# 7_-ADC_Chip.net
KiCad netlist of a schematic drawn in Altium Designer
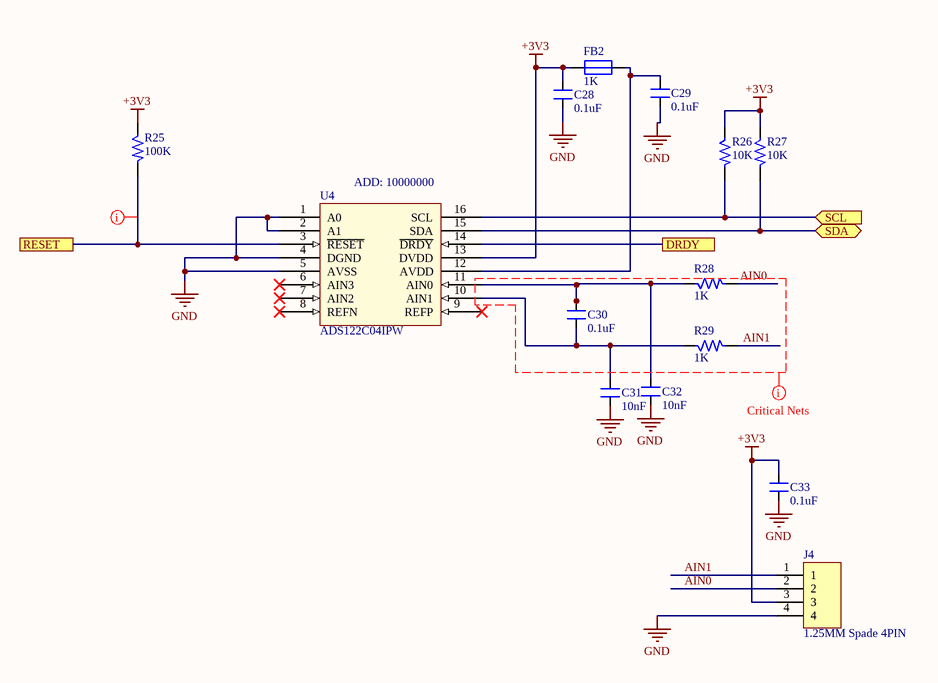
[diagram p0: (7)-ADC Chip.SchDoc]

(export (version "E")
  (design (tool "Eeschema 10.0.6"))
  (components
    (comp (ref "C28")
      (value "0.1uF")
      (footprint "CAP_0805")
      (description "0.1µF ±10% 50V Ceramic Capacitor X7R 0805 (2012 Metric)")
      (fields
        (field (name "MANUFACTURER") "Samsung")
        (field (name "MANUFACTURER PART NUMBER") "CL21B104KBCNNNC")
      )
      (libsource (lib "ESTEEMPCBLIB") (part "CAP_0.1uF-50V-10%-0805"))
    )
    (comp (ref "C29")
      (value "0.1uF")
      (footprint "CAP_0805")
      (description "0.1µF ±10% 50V Ceramic Capacitor X7R 0805 (2012 Metric)")
      (fields
        (field (name "MANUFACTURER") "Samsung")
        (field (name "MANUFACTURER PART NUMBER") "CL21B104KBCNNNC")
      )
      (libsource (lib "ESTEEMPCBLIB") (part "CAP_0.1uF-50V-10%-0805"))
    )
    (comp (ref "C30")
      (value "0.1uF")
      (footprint "CAP_0805")
      (description "0.1µF ±10% 50V Ceramic Capacitor X7R 0805 (2012 Metric)")
      (fields
        (field (name "MANUFACTURER") "Samsung")
        (field (name "MANUFACTURER PART NUMBER") "CL21B104KBCNNNC")
      )
      (libsource (lib "ESTEEMPCBLIB") (part "CAP_0.1uF-50V-10%-0805"))
    )
    (comp (ref "C31")
      (value "10nF")
      (footprint "CAP_0805")
      (description "10000pF ±10% 50V Ceramic Capacitor X7R 0805 (2012 Metric)")
      (fields
        (field (name "MANUFACTURER") "Samsung")
        (field (name "MANUFACTURER PART NUMBER") "C0805C103K5RECAUTO")
      )
      (libsource (lib "ESTEEMPCBLIB") (part "CAP_10nF-50V-10%-0805"))
    )
    (comp (ref "C32")
      (value "10nF")
      (footprint "CAP_0805")
      (description "10000pF ±10% 50V Ceramic Capacitor X7R 0805 (2012 Metric)")
      (fields
        (field (name "MANUFACTURER") "Samsung")
        (field (name "MANUFACTURER PART NUMBER") "C0805C103K5RECAUTO")
      )
      (libsource (lib "ESTEEMPCBLIB") (part "CAP_10nF-50V-10%-0805"))
    )
    (comp (ref "C33")
      (value "0.1uF")
      (footprint "CAP_0805")
      (description "0.1µF ±10% 50V Ceramic Capacitor X7R 0805 (2012 Metric)")
      (fields
        (field (name "MANUFACTURER") "Samsung")
        (field (name "MANUFACTURER PART NUMBER") "CL21B104KBCNNNC")
      )
      (libsource (lib "ESTEEMPCBLIB") (part "CAP_0.1uF-50V-10%-0805"))
    )
    (comp (ref "FB2")
      (value "1K")
      (footprint "IND_0805")
      (description "1 kOhms @ 100MHz 1 Power Line Ferrite Bead 0805 (2012 Metric) 1.6A")
      (fields
        (field (name "MANUFACTURER") "Laird")
        (field (name "MANUFACTURER PART NUMBER") "BLM21SP102SH1D")
      )
      (libsource (lib "ESTEEMPCBLIB") (part "FB_1K-100MHZ-1.6A-0805"))
    )
    (comp (ref "J4")
      (value "1.25MM Spade 4PIN")
      (footprint "CON4_50_653004117322_TH_RA")
      (description "4 Pins, 1 Row 1.25mm Pitch, right angle Connector, male")
      (fields (field (name "MANUFACTURER PART NUMBER") "653004117322") (field (name "MANUFACTURER") "JST"))
      (libsource (lib "ESTEEMPCBLIB") (part "CON-PLG_4X1-50-RA-TH"))
    )
    (comp (ref "R25")
      (value "100K")
      (footprint "RES_0603")
      (description "100 kOhms ±1% 0.1W, 1/10W Chip Resistor 0603 (1608 Metric) Automotive AEC-Q200 Thick Film")
      (fields
        (field (name "MANUFACTURER") "Stackpole Electronics")
        (field (name "MANUFACTURER PART NUMBER") "RMCF0603FT100K")
      )
      (libsource (lib "ESTEEMPCBLIB") (part "RES_100K-0.1W-1%-0603"))
    )
    (comp (ref "R26")
      (value "10K")
      (footprint "RES_0603")
      (description "10 kOhms ±1% 0.1W, 1/10W Chip Resistor 0603 (1608 Metric) Automotive AEC-Q200 Thick Film")
      (fields (field (name "MANUFACTURER") "Walsin") (field (name "MANUFACTURER PART NUMBER") "WR06X1002FTL"))
      (libsource (lib "ESTEEMPCBLIB") (part "RES_10K-0.1W-1%-0603"))
    )
    (comp (ref "R27")
      (value "10K")
      (footprint "RES_0603")
      (description "10 kOhms ±1% 0.1W, 1/10W Chip Resistor 0603 (1608 Metric) Automotive AEC-Q200 Thick Film")
      (fields (field (name "MANUFACTURER") "Walsin") (field (name "MANUFACTURER PART NUMBER") "WR06X1002FTL"))
      (libsource (lib "ESTEEMPCBLIB") (part "RES_10K-0.1W-1%-0603"))
    )
    (comp (ref "R28")
      (value "1K")
      (footprint "RES_0603")
      (description "1 kOhms ±1% 0.1W, 1/10W Chip Resistor 0603 (1608 Metric) Automotive AEC-Q200 Thick Film")
      (fields (field (name "MANUFACTURER") "Walsin") (field (name "MANUFACTURER PART NUMBER") "WR06X1001FTL"))
      (libsource (lib "ESTEEMPCBLIB") (part "RES_1K-0.1W-1%-0603"))
    )
    (comp (ref "R29")
      (value "1K")
      (footprint "RES_0603")
      (description "1 kOhms ±1% 0.1W, 1/10W Chip Resistor 0603 (1608 Metric) Automotive AEC-Q200 Thick Film")
      (fields (field (name "MANUFACTURER") "Walsin") (field (name "MANUFACTURER PART NUMBER") "WR06X1001FTL"))
      (libsource (lib "ESTEEMPCBLIB") (part "RES_1K-0.1W-1%-0603"))
    )
    (comp (ref "U4")
      (value "ADS122C04IPW")
      (footprint "TSSOP16_25-59_294_54X14_SMT")
      (description "24 Bit Analog to Digital Converter 4 Input 1 Sigma-Delta 16-TSSOP")
      (fields (field (name "MANUFACTURER") "Texas Instruments"))
      (libsource (lib "ESTEEMPCBLIB") (part "IC_ADS122C04IPW"))
    )
  )
  (nets
    (net (code "1") (name "+3V3") (class "Default")
      (node (ref "C28") (pin "2") (pinfunction "2_2") (pintype "passive"))
      (node (ref "C33") (pin "2") (pinfunction "2_2") (pintype "passive"))
      (node (ref "FB2") (pin "1") (pinfunction "1_1") (pintype "passive"))
      (node (ref "J4") (pin "3") (pinfunction "3_3") (pintype "passive"))
      (node (ref "R25") (pin "1") (pinfunction "1_1") (pintype "passive"))
      (node (ref "R26") (pin "1") (pinfunction "1_1") (pintype "passive"))
      (node (ref "R27") (pin "1") (pinfunction "1_1") (pintype "passive"))
      (node (ref "U4") (pin "13") (pinfunction "DVDD_13") (pintype "power_in"))
    )
    (net (code "2") (name "/AIN0") (class "Default")
      (node (ref "J4") (pin "2") (pinfunction "2_2") (pintype "passive"))
      (node (ref "R28") (pin "2") (pinfunction "2_2") (pintype "passive"))
    )
    (net (code "3") (name "/AIN1") (class "Default")
      (node (ref "J4") (pin "1") (pinfunction "1_1") (pintype "passive"))
      (node (ref "R29") (pin "2") (pinfunction "2_2") (pintype "passive"))
    )
    (net (code "4") (name "/DRDY") (class "Default")
      (node (ref "U4") (pin "14") (pinfunction "DRDY_14") (pintype "input"))
    )
    (net (code "5") (name "/RESET") (class "Default")
      (node (ref "R25") (pin "2") (pinfunction "2_2") (pintype "passive"))
      (node (ref "U4") (pin "3") (pinfunction "RESET_3") (pintype "input"))
    )
    (net (code "6") (name "/SCL") (class "Default")
      (node (ref "R26") (pin "2") (pinfunction "2_2") (pintype "passive"))
      (node (ref "U4") (pin "16") (pinfunction "SCL_16") (pintype "open_collector"))
    )
    (net (code "7") (name "/SDA") (class "Default")
      (node (ref "R27") (pin "2") (pinfunction "2_2") (pintype "passive"))
      (node (ref "U4") (pin "15") (pinfunction "SDA_15") (pintype "open_collector"))
    )
    (net (code "8") (name "GND") (class "Default")
      (node (ref "C28") (pin "1") (pinfunction "1_1") (pintype "passive"))
      (node (ref "C29") (pin "1") (pinfunction "1_1") (pintype "passive"))
      (node (ref "C31") (pin "2") (pinfunction "2_2") (pintype "passive"))
      (node (ref "C32") (pin "2") (pinfunction "2_2") (pintype "passive"))
      (node (ref "C33") (pin "1") (pinfunction "1_1") (pintype "passive"))
      (node (ref "J4") (pin "4") (pinfunction "4_4") (pintype "passive"))
      (node (ref "U4") (pin "1") (pinfunction "A0_1") (pintype "passive"))
      (node (ref "U4") (pin "2") (pinfunction "A1_2") (pintype "passive"))
      (node (ref "U4") (pin "4") (pinfunction "DGND_4") (pintype "power_in"))
      (node (ref "U4") (pin "5") (pinfunction "AVSS_5") (pintype "power_in"))
    )
    (net (code "9") (name "Net-(U4-AIN0)") (class "Default")
      (node (ref "C30") (pin "1") (pinfunction "1_1") (pintype "passive"))
      (node (ref "C32") (pin "1") (pinfunction "1_1") (pintype "passive"))
      (node (ref "R28") (pin "1") (pinfunction "1_1") (pintype "passive"))
      (node (ref "U4") (pin "11") (pinfunction "AIN0_11") (pintype "input"))
    )
    (net (code "10") (name "Net-(U4-AIN1)") (class "Default")
      (node (ref "C30") (pin "2") (pinfunction "2_2") (pintype "passive"))
      (node (ref "C31") (pin "1") (pinfunction "1_1") (pintype "passive"))
      (node (ref "R29") (pin "1") (pinfunction "1_1") (pintype "passive"))
      (node (ref "U4") (pin "10") (pinfunction "AIN1_10") (pintype "input"))
    )
    (net (code "11") (name "Net-(U4-AVDD)") (class "Default")
      (node (ref "C29") (pin "2") (pinfunction "2_2") (pintype "passive"))
      (node (ref "FB2") (pin "2") (pinfunction "2_2") (pintype "passive"))
      (node (ref "U4") (pin "12") (pinfunction "AVDD_12") (pintype "power_in"))
    )
    (net (code "12") (name "unconnected-(U4-AIN2-Pad7)") (class "Default")
      (node (ref "U4") (pin "7") (pinfunction "AIN2_7") (pintype "input+no_connect"))
    )
    (net (code "13") (name "unconnected-(U4-AIN3-Pad6)") (class "Default")
      (node (ref "U4") (pin "6") (pinfunction "AIN3_6") (pintype "input+no_connect"))
    )
    (net (code "14") (name "unconnected-(U4-REFN-Pad8)") (class "Default")
      (node (ref "U4") (pin "8") (pinfunction "REFN_8") (pintype "input+no_connect"))
    )
    (net (code "15") (name "unconnected-(U4-REFP-Pad9)") (class "Default")
      (node (ref "U4") (pin "9") (pinfunction "REFP_9") (pintype "input+no_connect"))
    )
  )
)
